# Rx1_0.net
KiCad netlist of a schematic drawn in EAGLE
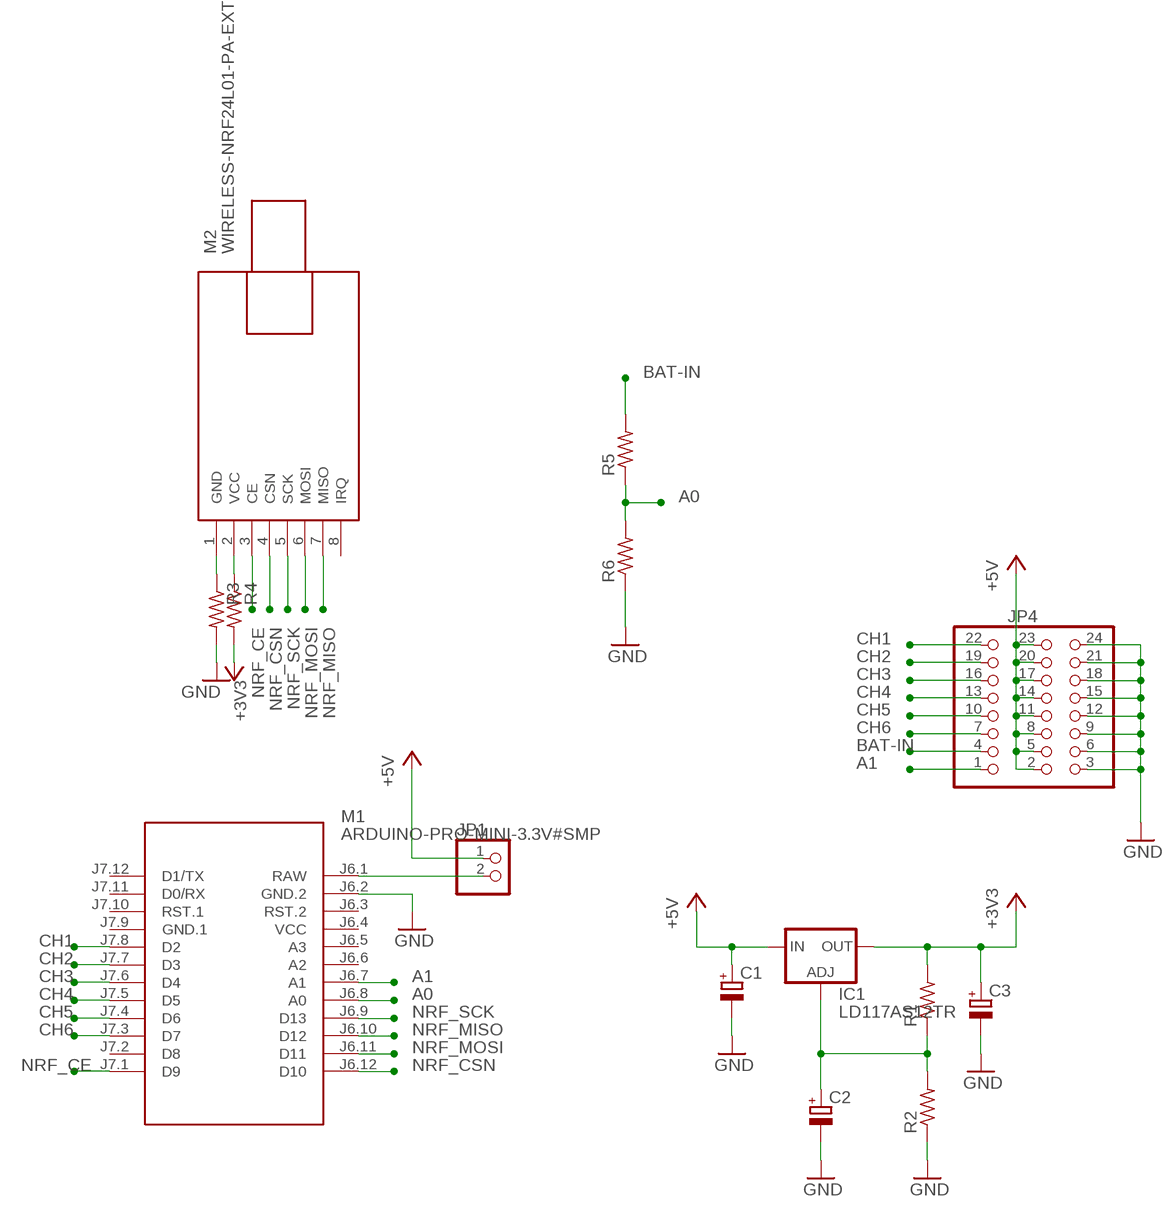
[diagram p0: schematic, sheet 1]

(export (version "E")
  (design (tool "Eeschema 10.0.6"))
  (components
    (comp (ref "C1")
      (value "CPOL-EUE1.8-4")
      (footprint "eagle-import:E1,8-4")
      (libsource (lib "eagle-import") (part "CPOL-EUE1.8-4"))
    )
    (comp (ref "C2")
      (value "CPOL-EUE1.8-4")
      (footprint "eagle-import:E1,8-4")
      (libsource (lib "eagle-import") (part "CPOL-EUE1.8-4"))
    )
    (comp (ref "C3")
      (value "CPOL-EUE1.8-4")
      (footprint "eagle-import:E1,8-4")
      (libsource (lib "eagle-import") (part "CPOL-EUE1.8-4"))
    )
    (comp (ref "IC1")
      (value "LD117AS12TR")
      (footprint "eagle-import:SOT223")
      (libsource (lib "eagle-import") (part "LD117A?S12TR"))
    )
    (comp (ref "JP1")
      (value "PINHD-1X2")
      (footprint "eagle-import:1X02")
      (libsource (lib "eagle-import") (part "PINHD-1X2"))
    )
    (comp (ref "JP4")
      (value "PINHD-3X8")
      (footprint "eagle-import:2X08")
      (libsource (lib "eagle-import") (part "PINHD-3X8"))
    )
    (comp (ref "M1")
      (value "ARDUINO-PRO-MINI-3.3V#SMP")
      (footprint "eagle-import:ARDUINO-PRO-MINI#SMP")
      (libsource (lib "eagle-import") (part "ARDUINO-PRO-MINI-#SMP3.3V"))
    )
    (comp (ref "M2")
      (value "WIRELESS-NRF24L01-PA-EXT")
      (footprint "eagle-import:WIRELESS-NRF24L01-PA-EXT")
      (libsource (lib "eagle-import") (part "WIRELESS-NRF24L01-PA-EXT"))
    )
    (comp (ref "R1")
      (value "R-US_0204/2V")
      (footprint "eagle-import:0204V")
      (libsource (lib "eagle-import") (part "R-US_0204/2V"))
    )
    (comp (ref "R2")
      (value "R-US_0204/2V")
      (footprint "eagle-import:0204V")
      (libsource (lib "eagle-import") (part "R-US_0204/2V"))
    )
    (comp (ref "R3")
      (value "R-US_0204/2V")
      (footprint "eagle-import:0204V")
      (libsource (lib "eagle-import") (part "R-US_0204/2V"))
    )
    (comp (ref "R4")
      (value "R-US_0204/2V")
      (footprint "eagle-import:0204V")
      (libsource (lib "eagle-import") (part "R-US_0204/2V"))
    )
    (comp (ref "R5")
      (value "R-US_0204/2V")
      (footprint "eagle-import:0204V")
      (libsource (lib "eagle-import") (part "R-US_0204/2V"))
    )
    (comp (ref "R6")
      (value "R-US_0204/2V")
      (footprint "eagle-import:0204V")
      (libsource (lib "eagle-import") (part "R-US_0204/2V"))
    )
  )
  (nets
    (net (code "1") (name "+3V3") (class "Default")
      (node (ref "C3") (pin "+") (pinfunction "+_+") (pintype "passive"))
      (node (ref "IC1") (pin "4") (pinfunction "OUT_4") (pintype "passive"))
      (node (ref "R1") (pin "2") (pinfunction "2_2") (pintype "passive"))
      (node (ref "R4") (pin "2") (pinfunction "2_2") (pintype "passive"))
    )
    (net (code "2") (name "+5V") (class "Default")
      (node (ref "C1") (pin "+") (pinfunction "+_+") (pintype "passive"))
      (node (ref "IC1") (pin "3") (pinfunction "IN_3") (pintype "input"))
      (node (ref "JP1") (pin "1") (pinfunction "1_1") (pintype "passive"))
      (node (ref "JP4") (pin "11") (pinfunction "11_11") (pintype "passive"))
      (node (ref "JP4") (pin "14") (pinfunction "14_14") (pintype "passive"))
      (node (ref "JP4") (pin "17") (pinfunction "17_17") (pintype "passive"))
      (node (ref "JP4") (pin "2") (pinfunction "2_2") (pintype "passive"))
      (node (ref "JP4") (pin "20") (pinfunction "20_20") (pintype "passive"))
      (node (ref "JP4") (pin "23") (pinfunction "23_23") (pintype "passive"))
      (node (ref "JP4") (pin "5") (pinfunction "5_5") (pintype "passive"))
      (node (ref "JP4") (pin "8") (pinfunction "8_8") (pintype "passive"))
    )
    (net (code "3") (name "/A0") (class "Default")
      (node (ref "M1") (pin "J6.8") (pinfunction "A0_J6.8") (pintype "bidirectional"))
      (node (ref "R5") (pin "1") (pinfunction "1_1") (pintype "passive"))
      (node (ref "R6") (pin "2") (pinfunction "2_2") (pintype "passive"))
    )
    (net (code "4") (name "/A1") (class "Default")
      (node (ref "JP4") (pin "1") (pinfunction "1_1") (pintype "passive"))
      (node (ref "M1") (pin "J6.7") (pinfunction "A1_J6.7") (pintype "bidirectional"))
    )
    (net (code "5") (name "/BAT-IN") (class "Default")
      (node (ref "JP4") (pin "4") (pinfunction "4_4") (pintype "passive"))
      (node (ref "R5") (pin "2") (pinfunction "2_2") (pintype "passive"))
    )
    (net (code "6") (name "/CH1") (class "Default")
      (node (ref "JP4") (pin "22") (pinfunction "22_22") (pintype "passive"))
      (node (ref "M1") (pin "J7.8") (pinfunction "D2_J7.8") (pintype "bidirectional"))
    )
    (net (code "7") (name "/CH2") (class "Default")
      (node (ref "JP4") (pin "19") (pinfunction "19_19") (pintype "passive"))
      (node (ref "M1") (pin "J7.7") (pinfunction "D3_J7.7") (pintype "bidirectional"))
    )
    (net (code "8") (name "/CH3") (class "Default")
      (node (ref "JP4") (pin "16") (pinfunction "16_16") (pintype "passive"))
      (node (ref "M1") (pin "J7.6") (pinfunction "D4_J7.6") (pintype "bidirectional"))
    )
    (net (code "9") (name "/CH4") (class "Default")
      (node (ref "JP4") (pin "13") (pinfunction "13_13") (pintype "passive"))
      (node (ref "M1") (pin "J7.5") (pinfunction "D5_J7.5") (pintype "bidirectional"))
    )
    (net (code "10") (name "/CH5") (class "Default")
      (node (ref "JP4") (pin "10") (pinfunction "10_10") (pintype "passive"))
      (node (ref "M1") (pin "J7.4") (pinfunction "D6_J7.4") (pintype "bidirectional"))
    )
    (net (code "11") (name "/CH6") (class "Default")
      (node (ref "JP4") (pin "7") (pinfunction "7_7") (pintype "passive"))
      (node (ref "M1") (pin "J7.3") (pinfunction "D7_J7.3") (pintype "bidirectional"))
    )
    (net (code "12") (name "/GND.1") (class "Default")
      (node (ref "M1") (pin "J7.9") (pinfunction "GND.1_J7.9") (pintype "power_in"))
    )
    (net (code "13") (name "/NRF_CE") (class "Default")
      (node (ref "M1") (pin "J7.1") (pinfunction "D9_J7.1") (pintype "bidirectional"))
      (node (ref "M2") (pin "3") (pinfunction "CE_3") (pintype "bidirectional"))
    )
    (net (code "14") (name "/NRF_CSN") (class "Default")
      (node (ref "M1") (pin "J6.12") (pinfunction "D10_J6.12") (pintype "bidirectional"))
      (node (ref "M2") (pin "4") (pinfunction "CSN_4") (pintype "bidirectional"))
    )
    (net (code "15") (name "/NRF_MISO") (class "Default")
      (node (ref "M1") (pin "J6.10") (pinfunction "D12_J6.10") (pintype "bidirectional"))
      (node (ref "M2") (pin "7") (pinfunction "MISO_7") (pintype "bidirectional"))
    )
    (net (code "16") (name "/NRF_MOSI") (class "Default")
      (node (ref "M1") (pin "J6.11") (pinfunction "D11_J6.11") (pintype "bidirectional"))
      (node (ref "M2") (pin "6") (pinfunction "MOSI_6") (pintype "bidirectional"))
    )
    (net (code "17") (name "/NRF_SCK") (class "Default")
      (node (ref "M1") (pin "J6.9") (pinfunction "D13_J6.9") (pintype "bidirectional"))
      (node (ref "M2") (pin "5") (pinfunction "SCK_5") (pintype "bidirectional"))
    )
    (net (code "18") (name "/VCC") (class "Default")
      (node (ref "M1") (pin "J6.4") (pinfunction "VCC_J6.4") (pintype "power_in"))
    )
    (net (code "19") (name "GND") (class "Default")
      (node (ref "C1") (pin "-") (pinfunction "-_-") (pintype "passive"))
      (node (ref "C2") (pin "-") (pinfunction "-_-") (pintype "passive"))
      (node (ref "C3") (pin "-") (pinfunction "-_-") (pintype "passive"))
      (node (ref "JP4") (pin "12") (pinfunction "12_12") (pintype "passive"))
      (node (ref "JP4") (pin "15") (pinfunction "15_15") (pintype "passive"))
      (node (ref "JP4") (pin "18") (pinfunction "18_18") (pintype "passive"))
      (node (ref "JP4") (pin "21") (pinfunction "21_21") (pintype "passive"))
      (node (ref "JP4") (pin "24") (pinfunction "24_24") (pintype "passive"))
      (node (ref "JP4") (pin "3") (pinfunction "3_3") (pintype "passive"))
      (node (ref "JP4") (pin "6") (pinfunction "6_6") (pintype "passive"))
      (node (ref "JP4") (pin "9") (pinfunction "9_9") (pintype "passive"))
      (node (ref "M1") (pin "J6.2") (pinfunction "GND.2_J6.2") (pintype "power_in"))
      (node (ref "R2") (pin "1") (pinfunction "1_1") (pintype "passive"))
      (node (ref "R3") (pin "2") (pinfunction "2_2") (pintype "passive"))
      (node (ref "R6") (pin "1") (pinfunction "1_1") (pintype "passive"))
    )
    (net (code "20") (name "Net-(IC1-ADJ)") (class "Default")
      (node (ref "C2") (pin "+") (pinfunction "+_+") (pintype "passive"))
      (node (ref "IC1") (pin "1") (pinfunction "ADJ_1") (pintype "input"))
      (node (ref "R1") (pin "1") (pinfunction "1_1") (pintype "passive"))
      (node (ref "R2") (pin "2") (pinfunction "2_2") (pintype "passive"))
    )
    (net (code "21") (name "Net-(M1-RAW)") (class "Default")
      (node (ref "JP1") (pin "2") (pinfunction "2_2") (pintype "passive"))
      (node (ref "M1") (pin "J6.1") (pinfunction "RAW_J6.1") (pintype "power_in"))
    )
    (net (code "22") (name "Net-(M2-GND)") (class "Default")
      (node (ref "M2") (pin "1") (pinfunction "GND_1") (pintype "power_in"))
      (node (ref "R3") (pin "1") (pinfunction "1_1") (pintype "passive"))
    )
    (net (code "23") (name "Net-(M2-VCC)") (class "Default")
      (node (ref "M2") (pin "2") (pinfunction "VCC_2") (pintype "power_in"))
      (node (ref "R4") (pin "1") (pinfunction "1_1") (pintype "passive"))
    )
    (net (code "24") (name "unconnected-(M1-A2-PadJ6.6)") (class "Default")
      (node (ref "M1") (pin "J6.6") (pinfunction "A2_J6.6") (pintype "bidirectional"))
    )
    (net (code "25") (name "unconnected-(M1-A3-PadJ6.5)") (class "Default")
      (node (ref "M1") (pin "J6.5") (pinfunction "A3_J6.5") (pintype "bidirectional"))
    )
    (net (code "26") (name "unconnected-(M1-D0{slash}RX-PadJ7.11)") (class "Default")
      (node (ref "M1") (pin "J7.11") (pinfunction "D0/RX_J7.11") (pintype "bidirectional"))
    )
    (net (code "27") (name "unconnected-(M1-D1{slash}TX-PadJ7.12)") (class "Default")
      (node (ref "M1") (pin "J7.12") (pinfunction "D1/TX_J7.12") (pintype "bidirectional"))
    )
    (net (code "28") (name "unconnected-(M1-D8-PadJ7.2)") (class "Default")
      (node (ref "M1") (pin "J7.2") (pinfunction "D8_J7.2") (pintype "bidirectional"))
    )
    (net (code "29") (name "unconnected-(M1-RST.1-PadJ7.10)") (class "Default")
      (node (ref "M1") (pin "J7.10") (pinfunction "RST.1_J7.10") (pintype "bidirectional"))
    )
    (net (code "30") (name "unconnected-(M1-RST.2-PadJ6.3)") (class "Default")
      (node (ref "M1") (pin "J6.3") (pinfunction "RST.2_J6.3") (pintype "bidirectional"))
    )
    (net (code "31") (name "unconnected-(M2-IRQ-Pad8)") (class "Default")
      (node (ref "M2") (pin "8") (pinfunction "IRQ_8") (pintype "bidirectional"))
    )
  )
)
